# XBee5.net
KiCad netlist of a schematic drawn in EAGLE
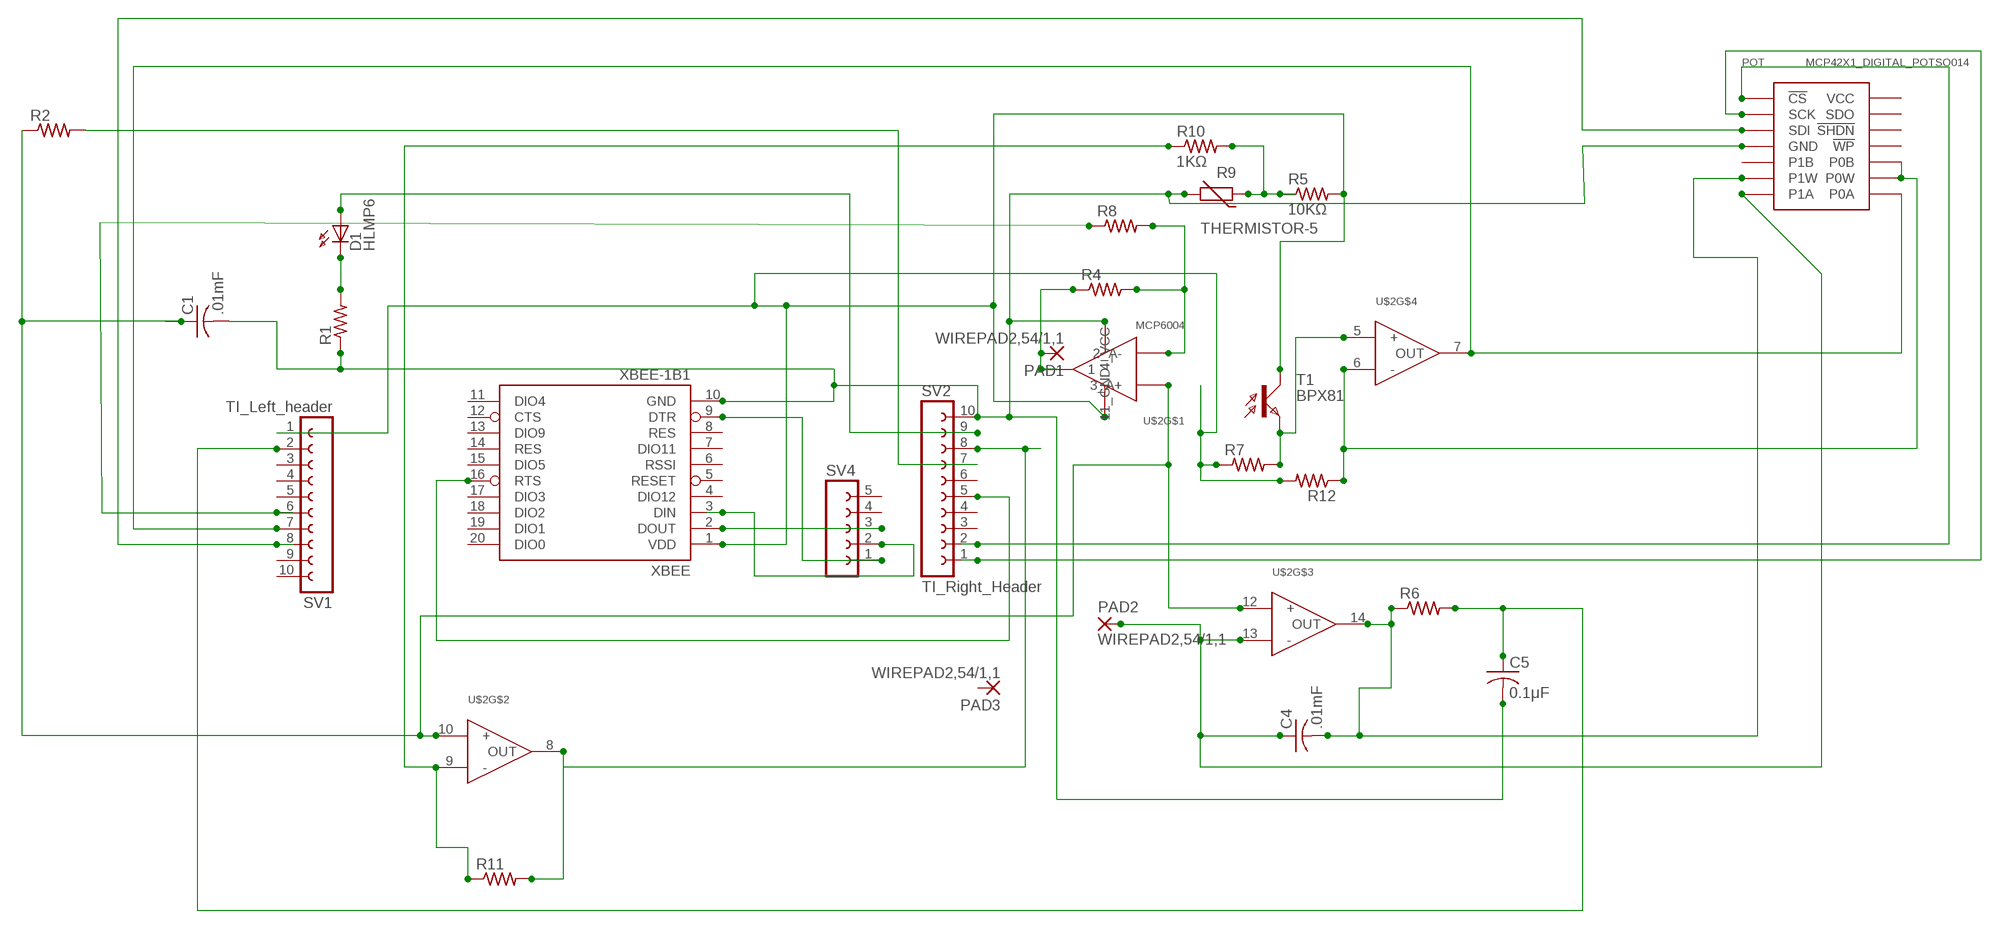
[diagram p0: schematic, sheet 1]

(export (version "E")
  (design (tool "Eeschema 10.0.6"))
  (components
    (comp (ref "C1")
      (value ".01mF")
      (footprint "eagle-import:C0603")
      (libsource (lib "eagle-import") (part "C-USC0603"))
    )
    (comp (ref "C4")
      (value ".01mF")
      (footprint "eagle-import:C0603")
      (libsource (lib "eagle-import") (part "C-USC0603"))
    )
    (comp (ref "C5")
      (value "0.1μF")
      (footprint "eagle-import:C0603")
      (libsource (lib "eagle-import") (part "C-USC0603"))
    )
    (comp (ref "D1")
      (value "HLMP6")
      (footprint "eagle-import:HLMP6")
      (fields (field (name "MF") "AGILENT TECHNOLOGIES") (field (name "MPN") "HLMP-6500"))
      (libsource (lib "eagle-import") (part "HLMP6"))
    )
    (comp (ref "PAD1")
      (value "WIREPAD2,54/1,1")
      (footprint "eagle-import:2,54_1,1")
      (libsource (lib "eagle-import") (part "WIREPAD2,54/1,1"))
    )
    (comp (ref "PAD2")
      (value "WIREPAD2,54/1,1")
      (footprint "eagle-import:2,54_1,1")
      (libsource (lib "eagle-import") (part "WIREPAD2,54/1,1"))
    )
    (comp (ref "PAD3")
      (value "WIREPAD2,54/1,1")
      (footprint "eagle-import:2,54_1,1")
      (libsource (lib "eagle-import") (part "WIREPAD2,54/1,1"))
    )
    (comp (ref "POT")
      (value "MCP42X1_DIGITAL_POTSO014")
      (footprint "eagle-import:SO014")
      (libsource (lib "eagle-import") (part "MCP42X1_DIGITAL_POTSO014"))
    )
    (comp (ref "R1")
      (value "R-US_R0603")
      (footprint "eagle-import:R0603")
      (libsource (lib "eagle-import") (part "R-US_R0603"))
    )
    (comp (ref "R2")
      (value "R-US_R0603")
      (footprint "eagle-import:R0603")
      (libsource (lib "eagle-import") (part "R-US_R0603"))
    )
    (comp (ref "R4")
      (value "R-US_R0603")
      (footprint "eagle-import:R0603")
      (libsource (lib "eagle-import") (part "R-US_R0603"))
    )
    (comp (ref "R5")
      (value "10KΩ")
      (footprint "eagle-import:R0603")
      (libsource (lib "eagle-import") (part "R-US_R0603"))
    )
    (comp (ref "R6")
      (value "R-US_R0603")
      (footprint "eagle-import:R0603")
      (libsource (lib "eagle-import") (part "R-US_R0603"))
    )
    (comp (ref "R7")
      (value "R-US_R0603")
      (footprint "eagle-import:R0603")
      (libsource (lib "eagle-import") (part "R-US_R0603"))
    )
    (comp (ref "R8")
      (value "R-US_R0603")
      (footprint "eagle-import:R0603")
      (libsource (lib "eagle-import") (part "R-US_R0603"))
    )
    (comp (ref "R9")
      (value "THERMISTOR-5")
      (footprint "eagle-import:R-5")
      (libsource (lib "eagle-import") (part "THERMISTOR-5"))
    )
    (comp (ref "R10")
      (value "1KΩ")
      (footprint "eagle-import:R0603")
      (libsource (lib "eagle-import") (part "R-US_R0603"))
    )
    (comp (ref "R11")
      (value "R-US_R0603")
      (footprint "eagle-import:R0603")
      (libsource (lib "eagle-import") (part "R-US_R0603"))
    )
    (comp (ref "R12")
      (value "R-US_R0603")
      (footprint "eagle-import:R0603")
      (libsource (lib "eagle-import") (part "R-US_R0603"))
    )
    (comp (ref "SV1")
      (value "TI_Left_header")
      (footprint "eagle-import:FE10")
      (libsource (lib "eagle-import") (part "FE10-1"))
    )
    (comp (ref "SV2")
      (value "TI_Right_Header")
      (footprint "eagle-import:FE10")
      (libsource (lib "eagle-import") (part "FE10-1"))
    )
    (comp (ref "SV4")
      (value "FE05-1")
      (footprint "eagle-import:FE05-1")
      (libsource (lib "eagle-import") (part "FE05-1"))
    )
    (comp (ref "T1")
      (value "BPX81")
      (footprint "eagle-import:BPX81")
      (libsource (lib "eagle-import") (part "BPX81"))
    )
    (comp (ref "U$2")
      (value "MCP6004")
      (footprint "eagle-import:SO014")
      (libsource (lib "eagle-import") (part "MCP6004"))
    )
    (comp (ref "XBEE")
      (value "XBEE-1B1")
      (footprint "eagle-import:XBEE-1")
      (libsource (lib "eagle-import") (part "XBEE-1B1"))
    )
  )
  (nets
    (net (code "1") (name "Net-(C5-Pad1)") (class "Default")
      (node (ref "C5") (pin "1") (pinfunction "1_1") (pintype "passive"))
      (node (ref "R6") (pin "2") (pinfunction "2_2") (pintype "passive"))
      (node (ref "SV1") (pin "2") (pinfunction "2_2") (pintype "passive"))
    )
    (net (code "2") (name "Net-(D1-PadA)") (class "Default")
      (node (ref "D1") (pin "A") (pinfunction "A_A") (pintype "passive"))
      (node (ref "SV2") (pin "9") (pinfunction "9_9") (pintype "passive"))
    )
    (net (code "3") (name "Net-(D1-PadK)") (class "Default")
      (node (ref "D1") (pin "K") (pinfunction "K_K") (pintype "passive"))
      (node (ref "R1") (pin "2") (pinfunction "2_2") (pintype "passive"))
    )
    (net (code "4") (name "Net-(PAD1-P)") (class "Default")
      (node (ref "PAD1") (pin "1") (pinfunction "P_1") (pintype "passive"))
      (node (ref "R4") (pin "1") (pinfunction "1_1") (pintype "passive"))
      (node (ref "U$2") (pin "1") (pinfunction "1_1") (pintype "bidirectional"))
    )
    (net (code "5") (name "Net-(PAD2-P)") (class "Default")
      (node (ref "C4") (pin "1") (pinfunction "1_1") (pintype "passive"))
      (node (ref "PAD2") (pin "1") (pinfunction "P_1") (pintype "passive"))
      (node (ref "POT") (pin "P7") (pinfunction "P1A_P7") (pintype "bidirectional"))
      (node (ref "U$2") (pin "13") (pinfunction "-_13") (pintype "bidirectional"))
    )
    (net (code "6") (name "Net-(POT-GND)") (class "Default")
      (node (ref "C1") (pin "2") (pinfunction "2_2") (pintype "passive"))
      (node (ref "C5") (pin "2") (pinfunction "2_2") (pintype "passive"))
      (node (ref "POT") (pin "P4") (pinfunction "GND_P4") (pintype "bidirectional"))
      (node (ref "R1") (pin "1") (pinfunction "1_1") (pintype "passive"))
      (node (ref "R9") (pin "2") (pinfunction "2_2") (pintype "passive"))
      (node (ref "SV2") (pin "10") (pinfunction "10_10") (pintype "passive"))
      (node (ref "U$2") (pin "11") (pinfunction "11_GND_11") (pintype "power_in"))
      (node (ref "XBEE") (pin "10") (pinfunction "GND_10") (pintype "power_in"))
    )
    (net (code "7") (name "Net-(POT-P0A)") (class "Default")
      (node (ref "POT") (pin "P8") (pinfunction "P0A_P8") (pintype "bidirectional"))
      (node (ref "SV1") (pin "7") (pinfunction "7_7") (pintype "passive"))
      (node (ref "U$2") (pin "7") (pinfunction "OUT_7") (pintype "bidirectional"))
    )
    (net (code "8") (name "Net-(POT-P0B)") (class "Default")
      (node (ref "POT") (pin "P10") (pinfunction "P0B_P10") (pintype "bidirectional"))
      (node (ref "POT") (pin "P9") (pinfunction "P0W_P9") (pintype "bidirectional"))
      (node (ref "R12") (pin "1") (pinfunction "1_1") (pintype "passive"))
      (node (ref "U$2") (pin "6") (pinfunction "-_6") (pintype "bidirectional"))
    )
    (net (code "9") (name "Net-(POT-P1W)") (class "Default")
      (node (ref "C4") (pin "2") (pinfunction "2_2") (pintype "passive"))
      (node (ref "POT") (pin "P6") (pinfunction "P1W_P6") (pintype "bidirectional"))
      (node (ref "R6") (pin "1") (pinfunction "1_1") (pintype "passive"))
      (node (ref "U$2") (pin "14") (pinfunction "OUT_14") (pintype "bidirectional"))
    )
    (net (code "10") (name "Net-(POT-SCK)") (class "Default")
      (node (ref "POT") (pin "P2") (pinfunction "SCK_P2") (pintype "bidirectional"))
      (node (ref "SV2") (pin "1") (pinfunction "1_1") (pintype "passive"))
    )
    (net (code "11") (name "Net-(POT-SDI)") (class "Default")
      (node (ref "POT") (pin "P3") (pinfunction "SDI_P3") (pintype "bidirectional"))
      (node (ref "SV1") (pin "8") (pinfunction "8_8") (pintype "passive"))
    )
    (net (code "12") (name "Net-(POT-~{CS})") (class "Default")
      (node (ref "POT") (pin "P1") (pinfunction "~{CS}_P1") (pintype "bidirectional"))
      (node (ref "SV2") (pin "2") (pinfunction "2_2") (pintype "passive"))
    )
    (net (code "13") (name "Net-(R2-Pad2)") (class "Default")
      (node (ref "R2") (pin "2") (pinfunction "2_2") (pintype "passive"))
      (node (ref "SV2") (pin "7") (pinfunction "7_7") (pintype "passive"))
    )
    (net (code "14") (name "Net-(R8-Pad1)") (class "Default")
      (node (ref "R8") (pin "1") (pinfunction "1_1") (pintype "passive"))
      (node (ref "SV1") (pin "6") (pinfunction "6_6") (pintype "passive"))
    )
    (net (code "15") (name "Net-(R10-Pad2)") (class "Default")
      (node (ref "R10") (pin "2") (pinfunction "2_2") (pintype "passive"))
      (node (ref "R5") (pin "1") (pinfunction "1_1") (pintype "passive"))
      (node (ref "R9") (pin "1") (pinfunction "1_1") (pintype "passive"))
    )
    (net (code "16") (name "Net-(U$2A-2_A-)") (class "Default")
      (node (ref "R4") (pin "2") (pinfunction "2_2") (pintype "passive"))
      (node (ref "R8") (pin "2") (pinfunction "2_2") (pintype "passive"))
      (node (ref "U$2") (pin "2") (pinfunction "2_A-_2") (pintype "bidirectional"))
    )
    (net (code "17") (name "Net-(U$2A-3_A+)") (class "Default")
      (node (ref "C1") (pin "1") (pinfunction "1_1") (pintype "passive"))
      (node (ref "R2") (pin "1") (pinfunction "1_1") (pintype "passive"))
      (node (ref "U$2") (pin "10") (pinfunction "+_10") (pintype "bidirectional"))
      (node (ref "U$2") (pin "12") (pinfunction "+_12") (pintype "bidirectional"))
      (node (ref "U$2") (pin "3") (pinfunction "3_A+_3") (pintype "bidirectional"))
    )
    (net (code "18") (name "Net-(U$2A-4_VCC)") (class "Default")
      (node (ref "R12") (pin "2") (pinfunction "2_2") (pintype "passive"))
      (node (ref "R5") (pin "2") (pinfunction "2_2") (pintype "passive"))
      (node (ref "R7") (pin "1") (pinfunction "1_1") (pintype "passive"))
      (node (ref "SV1") (pin "1") (pinfunction "1_1") (pintype "passive"))
      (node (ref "T1") (pin "C") (pinfunction "C_C") (pintype "passive"))
      (node (ref "U$2") (pin "4") (pinfunction "4_VCC_4") (pintype "power_in"))
      (node (ref "XBEE") (pin "1") (pinfunction "VDD_1") (pintype "power_in"))
    )
    (net (code "19") (name "Net-(U$2B--)") (class "Default")
      (node (ref "R10") (pin "1") (pinfunction "1_1") (pintype "passive"))
      (node (ref "R11") (pin "1") (pinfunction "1_1") (pintype "passive"))
      (node (ref "U$2") (pin "9") (pinfunction "-_9") (pintype "bidirectional"))
    )
    (net (code "20") (name "Net-(U$2B-OUT)") (class "Default")
      (node (ref "R11") (pin "2") (pinfunction "2_2") (pintype "passive"))
      (node (ref "SV2") (pin "8") (pinfunction "8_8") (pintype "passive"))
      (node (ref "U$2") (pin "8") (pinfunction "OUT_8") (pintype "bidirectional"))
    )
    (net (code "21") (name "Net-(U$2D-+)") (class "Default")
      (node (ref "R7") (pin "2") (pinfunction "2_2") (pintype "passive"))
      (node (ref "T1") (pin "E") (pinfunction "E_E") (pintype "passive"))
      (node (ref "U$2") (pin "5") (pinfunction "+_5") (pintype "bidirectional"))
    )
    (net (code "22") (name "Net-(XBEE-DIN)") (class "Default")
      (node (ref "SV4") (pin "2") (pinfunction "2_2") (pintype "passive"))
      (node (ref "XBEE") (pin "3") (pinfunction "DIN_3") (pintype "input"))
    )
    (net (code "23") (name "Net-(XBEE-DOUT)") (class "Default")
      (node (ref "SV4") (pin "3") (pinfunction "3_3") (pintype "passive"))
      (node (ref "XBEE") (pin "2") (pinfunction "DOUT_2") (pintype "output"))
    )
    (net (code "24") (name "Net-(XBEE-DTR)") (class "Default")
      (node (ref "SV4") (pin "1") (pinfunction "1_1") (pintype "passive"))
      (node (ref "XBEE") (pin "9") (pinfunction "DTR_9") (pintype "bidirectional"))
    )
    (net (code "25") (name "Net-(XBEE-RTS)") (class "Default")
      (node (ref "SV2") (pin "5") (pinfunction "5_5") (pintype "passive"))
      (node (ref "XBEE") (pin "16") (pinfunction "RTS_16") (pintype "input"))
    )
    (net (code "26") (name "unconnected-(PAD3-P-Pad1)") (class "Default")
      (node (ref "PAD3") (pin "1") (pinfunction "P_1") (pintype "passive"))
    )
    (net (code "27") (name "unconnected-(POT-P1B-PadP5)") (class "Default")
      (node (ref "POT") (pin "P5") (pinfunction "P1B_P5") (pintype "bidirectional"))
    )
    (net (code "28") (name "unconnected-(POT-SDO-PadP13)") (class "Default")
      (node (ref "POT") (pin "P13") (pinfunction "SDO_P13") (pintype "bidirectional"))
    )
    (net (code "29") (name "unconnected-(POT-VCC-PadP14)") (class "Default")
      (node (ref "POT") (pin "P14") (pinfunction "VCC_P14") (pintype "bidirectional"))
    )
    (net (code "30") (name "unconnected-(POT-~{SHDN}-PadP12)") (class "Default")
      (node (ref "POT") (pin "P12") (pinfunction "~{SHDN}_P12") (pintype "bidirectional"))
    )
    (net (code "31") (name "unconnected-(POT-~{WP}-PadP11)") (class "Default")
      (node (ref "POT") (pin "P11") (pinfunction "~{WP}_P11") (pintype "bidirectional"))
    )
    (net (code "32") (name "unconnected-(SV1-Pad3)") (class "Default")
      (node (ref "SV1") (pin "3") (pinfunction "3_3") (pintype "passive"))
    )
    (net (code "33") (name "unconnected-(SV1-Pad4)") (class "Default")
      (node (ref "SV1") (pin "4") (pinfunction "4_4") (pintype "passive"))
    )
    (net (code "34") (name "unconnected-(SV1-Pad5)") (class "Default")
      (node (ref "SV1") (pin "5") (pinfunction "5_5") (pintype "passive"))
    )
    (net (code "35") (name "unconnected-(SV1-Pad9)") (class "Default")
      (node (ref "SV1") (pin "9") (pinfunction "9_9") (pintype "passive"))
    )
    (net (code "36") (name "unconnected-(SV1-Pad10)") (class "Default")
      (node (ref "SV1") (pin "10") (pinfunction "10_10") (pintype "passive"))
    )
    (net (code "37") (name "unconnected-(SV2-Pad3)") (class "Default")
      (node (ref "SV2") (pin "3") (pinfunction "3_3") (pintype "passive"))
    )
    (net (code "38") (name "unconnected-(SV2-Pad4)") (class "Default")
      (node (ref "SV2") (pin "4") (pinfunction "4_4") (pintype "passive"))
    )
    (net (code "39") (name "unconnected-(SV2-Pad6)") (class "Default")
      (node (ref "SV2") (pin "6") (pinfunction "6_6") (pintype "passive"))
    )
    (net (code "40") (name "unconnected-(SV4-Pad4)") (class "Default")
      (node (ref "SV4") (pin "4") (pinfunction "4_4") (pintype "passive"))
    )
    (net (code "41") (name "unconnected-(SV4-Pad5)") (class "Default")
      (node (ref "SV4") (pin "5") (pinfunction "5_5") (pintype "passive"))
    )
    (net (code "42") (name "unconnected-(XBEE-CTS-Pad12)") (class "Default")
      (node (ref "XBEE") (pin "12") (pinfunction "CTS_12") (pintype "output"))
    )
    (net (code "43") (name "unconnected-(XBEE-DIO0-Pad20)") (class "Default")
      (node (ref "XBEE") (pin "20") (pinfunction "DIO0_20") (pintype "bidirectional"))
    )
    (net (code "44") (name "unconnected-(XBEE-DIO1-Pad19)") (class "Default")
      (node (ref "XBEE") (pin "19") (pinfunction "DIO1_19") (pintype "bidirectional"))
    )
    (net (code "45") (name "unconnected-(XBEE-DIO2-Pad18)") (class "Default")
      (node (ref "XBEE") (pin "18") (pinfunction "DIO2_18") (pintype "bidirectional"))
    )
    (net (code "46") (name "unconnected-(XBEE-DIO3-Pad17)") (class "Default")
      (node (ref "XBEE") (pin "17") (pinfunction "DIO3_17") (pintype "bidirectional"))
    )
    (net (code "47") (name "unconnected-(XBEE-DIO4-Pad11)") (class "Default")
      (node (ref "XBEE") (pin "11") (pinfunction "DIO4_11") (pintype "bidirectional"))
    )
    (net (code "48") (name "unconnected-(XBEE-DIO5-Pad15)") (class "Default")
      (node (ref "XBEE") (pin "15") (pinfunction "DIO5_15") (pintype "bidirectional"))
    )
    (net (code "49") (name "unconnected-(XBEE-DIO9-Pad13)") (class "Default")
      (node (ref "XBEE") (pin "13") (pinfunction "DIO9_13") (pintype "bidirectional"))
    )
    (net (code "50") (name "unconnected-(XBEE-DIO11-Pad7)") (class "Default")
      (node (ref "XBEE") (pin "7") (pinfunction "DIO11_7") (pintype "bidirectional"))
    )
    (net (code "51") (name "unconnected-(XBEE-DIO12-Pad4)") (class "Default")
      (node (ref "XBEE") (pin "4") (pinfunction "DIO12_4") (pintype "bidirectional"))
    )
    (net (code "52") (name "unconnected-(XBEE-RES-Pad8)") (class "Default")
      (node (ref "XBEE") (pin "8") (pinfunction "RES_8") (pintype "bidirectional"))
    )
    (net (code "53") (name "unconnected-(XBEE-RES-Pad14)") (class "Default")
      (node (ref "XBEE") (pin "14") (pinfunction "RES_14") (pintype "bidirectional"))
    )
    (net (code "54") (name "unconnected-(XBEE-RESET-Pad5)") (class "Default")
      (node (ref "XBEE") (pin "5") (pinfunction "RESET_5") (pintype "input"))
    )
    (net (code "55") (name "unconnected-(XBEE-RSSI-Pad6)") (class "Default")
      (node (ref "XBEE") (pin "6") (pinfunction "RSSI_6") (pintype "bidirectional"))
    )
  )
)
